# DMS_fullbridge.net
KiCad netlist of a schematic drawn in EAGLE
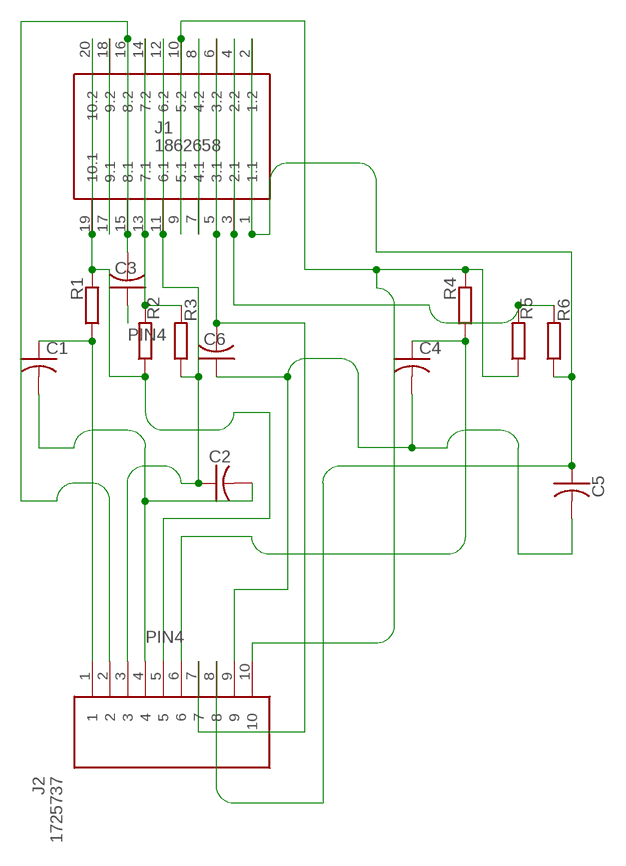
[diagram p0: schematic, sheet 1]

(export (version "E")
  (design (tool "Eeschema 10.0.6"))
  (components
    (comp (ref "C1")
      (value "C-US050-030X075")
      (footprint "eagle-import:C050-030X075")
      (libsource (lib "eagle-import") (part "C-US050-030X075"))
    )
    (comp (ref "C2")
      (value "C-US050-030X075")
      (footprint "eagle-import:C050-030X075")
      (libsource (lib "eagle-import") (part "C-US050-030X075"))
    )
    (comp (ref "C3")
      (value "C-US050-030X075")
      (footprint "eagle-import:C050-030X075")
      (libsource (lib "eagle-import") (part "C-US050-030X075"))
    )
    (comp (ref "C4")
      (value "C-US050-030X075")
      (footprint "eagle-import:C050-030X075")
      (libsource (lib "eagle-import") (part "C-US050-030X075"))
    )
    (comp (ref "C5")
      (value "C-US050-030X075")
      (footprint "eagle-import:C050-030X075")
      (libsource (lib "eagle-import") (part "C-US050-030X075"))
    )
    (comp (ref "C6")
      (value "C-US050-030X075")
      (footprint "eagle-import:C050-030X075")
      (libsource (lib "eagle-import") (part "C-US050-030X075"))
    )
    (comp (ref "J1")
      (value "1862658")
      (footprint "eagle-import:1862658")
      (fields (field (name "MOUSER_PART_NUMBER") "651-1862658"))
      (libsource (lib "eagle-import") (part "1862658"))
    )
    (comp (ref "J2")
      (value "1725737")
      (footprint "eagle-import:1725737")
      (fields (field (name "MOUSER_PART_NUMBER") "651-1725737"))
      (libsource (lib "eagle-import") (part "1725737"))
    )
    (comp (ref "R1")
      (value "R-EU_0204/7")
      (footprint "eagle-import:0204_7")
      (libsource (lib "eagle-import") (part "R-EU_0204/7"))
    )
    (comp (ref "R2")
      (value "R-EU_0204/7")
      (footprint "eagle-import:0204_7")
      (libsource (lib "eagle-import") (part "R-EU_0204/7"))
    )
    (comp (ref "R3")
      (value "R-EU_0204/7")
      (footprint "eagle-import:0204_7")
      (libsource (lib "eagle-import") (part "R-EU_0204/7"))
    )
    (comp (ref "R4")
      (value "R-EU_0204/7")
      (footprint "eagle-import:0204_7")
      (libsource (lib "eagle-import") (part "R-EU_0204/7"))
    )
    (comp (ref "R5")
      (value "R-EU_0204/7")
      (footprint "eagle-import:0204_7")
      (libsource (lib "eagle-import") (part "R-EU_0204/7"))
    )
    (comp (ref "R6")
      (value "R-EU_0204/7")
      (footprint "eagle-import:0204_7")
      (libsource (lib "eagle-import") (part "R-EU_0204/7"))
    )
  )
  (nets
    (net (code "1") (name "/ONE") (class "Default")
      (node (ref "C1") (pin "1") (pinfunction "1_1") (pintype "passive"))
      (node (ref "C4") (pin "1") (pinfunction "1_1") (pintype "passive"))
      (node (ref "J2") (pin "1") (pinfunction "1_1") (pintype "bidirectional"))
      (node (ref "J2") (pin "6") (pinfunction "6_6") (pintype "bidirectional"))
      (node (ref "R1") (pin "1") (pinfunction "1_1") (pintype "passive"))
      (node (ref "R4") (pin "1") (pinfunction "1_1") (pintype "passive"))
    )
    (net (code "2") (name "/PIN4") (class "Default")
      (node (ref "C1") (pin "2") (pinfunction "2_2") (pintype "passive"))
      (node (ref "C2") (pin "2") (pinfunction "2_2") (pintype "passive"))
      (node (ref "C3") (pin "1") (pinfunction "1_1") (pintype "passive"))
      (node (ref "J2") (pin "4") (pinfunction "4_4") (pintype "bidirectional"))
    )
    (net (code "3") (name "Net-(C4-Pad2)") (class "Default")
      (node (ref "C4") (pin "2") (pinfunction "2_2") (pintype "passive"))
      (node (ref "C5") (pin "2") (pinfunction "2_2") (pintype "passive"))
      (node (ref "C6") (pin "1") (pinfunction "1_1") (pintype "passive"))
      (node (ref "J2") (pin "9") (pinfunction "9_9") (pintype "bidirectional"))
    )
    (net (code "4") (name "Net-(J1-1.1)") (class "Default")
      (node (ref "C5") (pin "1") (pinfunction "1_1") (pintype "passive"))
      (node (ref "J1") (pin "1") (pinfunction "1.1_1") (pintype "bidirectional"))
      (node (ref "J1") (pin "2") (pinfunction "1.2_2") (pintype "bidirectional"))
      (node (ref "J2") (pin "8") (pinfunction "8_8") (pintype "bidirectional"))
      (node (ref "R6") (pin "1") (pinfunction "1_1") (pintype "passive"))
    )
    (net (code "5") (name "Net-(J1-2.1)") (class "Default")
      (node (ref "J1") (pin "3") (pinfunction "2.1_3") (pintype "bidirectional"))
      (node (ref "J1") (pin "4") (pinfunction "2.2_4") (pintype "bidirectional"))
      (node (ref "R5") (pin "2") (pinfunction "2_2") (pintype "passive"))
      (node (ref "R6") (pin "2") (pinfunction "2_2") (pintype "passive"))
    )
    (net (code "6") (name "Net-(J1-3.1)") (class "Default")
      (node (ref "C6") (pin "2") (pinfunction "2_2") (pintype "passive"))
      (node (ref "J1") (pin "5") (pinfunction "3.1_5") (pintype "bidirectional"))
      (node (ref "J1") (pin "6") (pinfunction "3.2_6") (pintype "bidirectional"))
      (node (ref "J2") (pin "7") (pinfunction "7_7") (pintype "bidirectional"))
    )
    (net (code "7") (name "Net-(J1-4.1)") (class "Default")
      (node (ref "J1") (pin "7") (pinfunction "4.1_7") (pintype "bidirectional"))
      (node (ref "J1") (pin "8") (pinfunction "4.2_8") (pintype "bidirectional"))
    )
    (net (code "8") (name "Net-(J1-5.1)") (class "Default")
      (node (ref "J1") (pin "10") (pinfunction "5.2_10") (pintype "bidirectional"))
      (node (ref "J1") (pin "9") (pinfunction "5.1_9") (pintype "bidirectional"))
      (node (ref "J2") (pin "10") (pinfunction "10_10") (pintype "bidirectional"))
      (node (ref "R4") (pin "2") (pinfunction "2_2") (pintype "passive"))
      (node (ref "R5") (pin "1") (pinfunction "1_1") (pintype "passive"))
    )
    (net (code "9") (name "Net-(J1-6.1)") (class "Default")
      (node (ref "C2") (pin "1") (pinfunction "1_1") (pintype "passive"))
      (node (ref "J1") (pin "11") (pinfunction "6.1_11") (pintype "bidirectional"))
      (node (ref "J1") (pin "12") (pinfunction "6.2_12") (pintype "bidirectional"))
      (node (ref "J2") (pin "3") (pinfunction "3_3") (pintype "bidirectional"))
      (node (ref "R3") (pin "1") (pinfunction "1_1") (pintype "passive"))
    )
    (net (code "10") (name "Net-(J1-7.1)") (class "Default")
      (node (ref "J1") (pin "13") (pinfunction "7.1_13") (pintype "bidirectional"))
      (node (ref "J1") (pin "14") (pinfunction "7.2_14") (pintype "bidirectional"))
      (node (ref "R2") (pin "2") (pinfunction "2_2") (pintype "passive"))
      (node (ref "R3") (pin "2") (pinfunction "2_2") (pintype "passive"))
    )
    (net (code "11") (name "Net-(J1-8.1)") (class "Default")
      (node (ref "C3") (pin "2") (pinfunction "2_2") (pintype "passive"))
      (node (ref "J1") (pin "15") (pinfunction "8.1_15") (pintype "bidirectional"))
      (node (ref "J1") (pin "16") (pinfunction "8.2_16") (pintype "bidirectional"))
      (node (ref "J2") (pin "2") (pinfunction "2_2") (pintype "bidirectional"))
    )
    (net (code "12") (name "Net-(J1-9.1)") (class "Default")
      (node (ref "J1") (pin "17") (pinfunction "9.1_17") (pintype "bidirectional"))
      (node (ref "J1") (pin "18") (pinfunction "9.2_18") (pintype "bidirectional"))
    )
    (net (code "13") (name "Net-(J1-10.1)") (class "Default")
      (node (ref "J1") (pin "19") (pinfunction "10.1_19") (pintype "bidirectional"))
      (node (ref "J1") (pin "20") (pinfunction "10.2_20") (pintype "bidirectional"))
      (node (ref "J2") (pin "5") (pinfunction "5_5") (pintype "bidirectional"))
      (node (ref "R1") (pin "2") (pinfunction "2_2") (pintype "passive"))
      (node (ref "R2") (pin "1") (pinfunction "1_1") (pintype "passive"))
    )
  )
)
